# rfm69_carrier_leftside.net
KiCad netlist of a schematic drawn in EAGLE
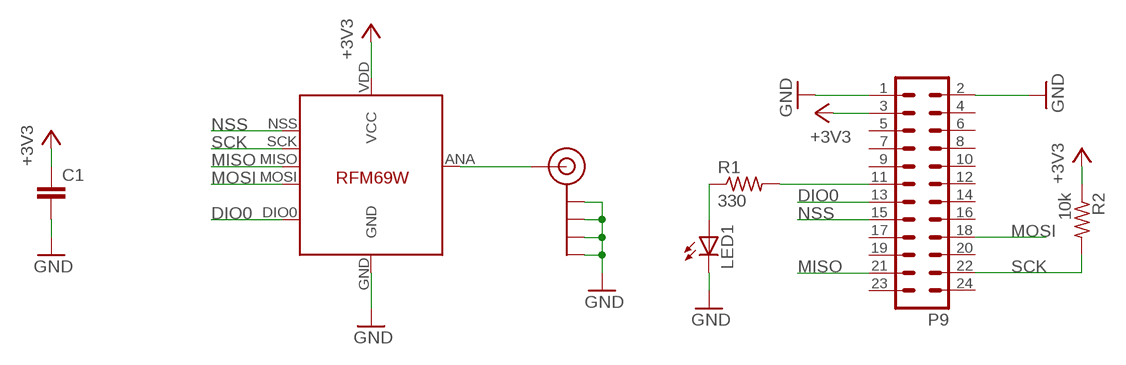
[diagram p0: schematic, sheet 1]

(export (version "E")
  (design (tool "Eeschema 10.0.6"))
  (components
    (comp (ref "ANT")
      (value "SMA_EDGE")
      (footprint "eagle-import:SMA-EDGE")
      (libsource (lib "eagle-import") (part "SMA_EDGE"))
    )
    (comp (ref "C1")
      (value "C-EUC1206")
      (footprint "eagle-import:C1206")
      (libsource (lib "eagle-import") (part "C-EUC1206"))
    )
    (comp (ref "LED1")
      (value "LEDCHIP-LED0805")
      (footprint "eagle-import:CHIP-LED0805")
      (libsource (lib "eagle-import") (part "LEDCHIP-LED0805"))
    )
    (comp (ref "P9")
      (value "MA12-2W")
      (footprint "eagle-import:MA12-2W")
      (libsource (lib "eagle-import") (part "MA12-2W"))
    )
    (comp (ref "R1")
      (value "330")
      (footprint "eagle-import:R0603")
      (libsource (lib "eagle-import") (part "R-US_R0603"))
    )
    (comp (ref "R2")
      (value "10k")
      (footprint "eagle-import:R0603")
      (libsource (lib "eagle-import") (part "R-US_R0603"))
    )
    (comp (ref "U1")
      (value "RFM69")
      (footprint "eagle-import:RFM69W-MINPADS")
      (libsource (lib "eagle-import") (part "RFM69"))
    )
  )
  (nets
    (net (code "1") (name "+3V3") (class "Default")
      (node (ref "C1") (pin "1") (pinfunction "1_1") (pintype "passive"))
      (node (ref "P9") (pin "3") (pinfunction "3_3") (pintype "passive"))
      (node (ref "R2") (pin "1") (pinfunction "1_1") (pintype "passive"))
      (node (ref "U1") (pin "VDD") (pinfunction "VCC_VDD") (pintype "power_in"))
    )
    (net (code "2") (name "/DIO0") (class "Default")
      (node (ref "P9") (pin "13") (pinfunction "13_13") (pintype "passive"))
      (node (ref "U1") (pin "DIO0") (pinfunction "DIO0_DIO0") (pintype "open_collector"))
    )
    (net (code "3") (name "/MISO") (class "Default")
      (node (ref "P9") (pin "21") (pinfunction "21_21") (pintype "passive"))
      (node (ref "U1") (pin "MISO") (pinfunction "MISO_MISO") (pintype "input"))
    )
    (net (code "4") (name "/MOSI") (class "Default")
      (node (ref "P9") (pin "18") (pinfunction "18_18") (pintype "passive"))
      (node (ref "U1") (pin "MOSI") (pinfunction "MOSI_MOSI") (pintype "output"))
    )
    (net (code "5") (name "/NSS") (class "Default")
      (node (ref "P9") (pin "15") (pinfunction "15_15") (pintype "passive"))
      (node (ref "U1") (pin "NSS") (pinfunction "SEL_NSS") (pintype "input"))
    )
    (net (code "6") (name "/SCK") (class "Default")
      (node (ref "P9") (pin "22") (pinfunction "22_22") (pintype "passive"))
      (node (ref "R2") (pin "2") (pinfunction "2_2") (pintype "passive"))
      (node (ref "U1") (pin "SCK") (pinfunction "SCK_SCK") (pintype "input"))
    )
    (net (code "7") (name "GND") (class "Default")
      (node (ref "ANT") (pin "GND@0") (pinfunction "GND_GND@0") (pintype "bidirectional"))
      (node (ref "ANT") (pin "GND@1") (pinfunction "GND_GND@1") (pintype "bidirectional"))
      (node (ref "ANT") (pin "GND@2") (pinfunction "GND_GND@2") (pintype "bidirectional"))
      (node (ref "ANT") (pin "GND@3") (pinfunction "GND_GND@3") (pintype "bidirectional"))
      (node (ref "C1") (pin "2") (pinfunction "2_2") (pintype "passive"))
      (node (ref "LED1") (pin "C") (pinfunction "C_C") (pintype "passive"))
      (node (ref "P9") (pin "1") (pinfunction "1_1") (pintype "passive"))
      (node (ref "P9") (pin "2") (pinfunction "2_2") (pintype "passive"))
      (node (ref "U1") (pin "GND") (pinfunction "GND_GND") (pintype "power_in"))
    )
    (net (code "8") (name "Net-(ANT-SIGNAL)") (class "Default")
      (node (ref "ANT") (pin "SIG") (pinfunction "SIGNAL_SIG") (pintype "bidirectional"))
      (node (ref "U1") (pin "ANA") (pinfunction "ANT_ANA") (pintype "passive"))
    )
    (net (code "9") (name "Net-(LED1-PadA)") (class "Default")
      (node (ref "LED1") (pin "A") (pinfunction "A_A") (pintype "passive"))
      (node (ref "R1") (pin "1") (pinfunction "1_1") (pintype "passive"))
    )
    (net (code "10") (name "Net-(P9-Pad11)") (class "Default")
      (node (ref "P9") (pin "11") (pinfunction "11_11") (pintype "passive"))
      (node (ref "R1") (pin "2") (pinfunction "2_2") (pintype "passive"))
    )
    (net (code "11") (name "unconnected-(P9-Pad4)") (class "Default")
      (node (ref "P9") (pin "4") (pinfunction "4_4") (pintype "passive"))
    )
    (net (code "12") (name "unconnected-(P9-Pad5)") (class "Default")
      (node (ref "P9") (pin "5") (pinfunction "5_5") (pintype "passive"))
    )
    (net (code "13") (name "unconnected-(P9-Pad6)") (class "Default")
      (node (ref "P9") (pin "6") (pinfunction "6_6") (pintype "passive"))
    )
    (net (code "14") (name "unconnected-(P9-Pad7)") (class "Default")
      (node (ref "P9") (pin "7") (pinfunction "7_7") (pintype "passive"))
    )
    (net (code "15") (name "unconnected-(P9-Pad8)") (class "Default")
      (node (ref "P9") (pin "8") (pinfunction "8_8") (pintype "passive"))
    )
    (net (code "16") (name "unconnected-(P9-Pad9)") (class "Default")
      (node (ref "P9") (pin "9") (pinfunction "9_9") (pintype "passive"))
    )
    (net (code "17") (name "unconnected-(P9-Pad10)") (class "Default")
      (node (ref "P9") (pin "10") (pinfunction "10_10") (pintype "passive"))
    )
    (net (code "18") (name "unconnected-(P9-Pad12)") (class "Default")
      (node (ref "P9") (pin "12") (pinfunction "12_12") (pintype "passive"))
    )
    (net (code "19") (name "unconnected-(P9-Pad14)") (class "Default")
      (node (ref "P9") (pin "14") (pinfunction "14_14") (pintype "passive"))
    )
    (net (code "20") (name "unconnected-(P9-Pad16)") (class "Default")
      (node (ref "P9") (pin "16") (pinfunction "16_16") (pintype "passive"))
    )
    (net (code "21") (name "unconnected-(P9-Pad17)") (class "Default")
      (node (ref "P9") (pin "17") (pinfunction "17_17") (pintype "passive"))
    )
    (net (code "22") (name "unconnected-(P9-Pad19)") (class "Default")
      (node (ref "P9") (pin "19") (pinfunction "19_19") (pintype "passive"))
    )
    (net (code "23") (name "unconnected-(P9-Pad20)") (class "Default")
      (node (ref "P9") (pin "20") (pinfunction "20_20") (pintype "passive"))
    )
    (net (code "24") (name "unconnected-(P9-Pad23)") (class "Default")
      (node (ref "P9") (pin "23") (pinfunction "23_23") (pintype "passive"))
    )
    (net (code "25") (name "unconnected-(P9-Pad24)") (class "Default")
      (node (ref "P9") (pin "24") (pinfunction "24_24") (pintype "passive"))
    )
  )
)
